# CarPower.net
KiCad netlist of a schematic drawn in Altium Designer
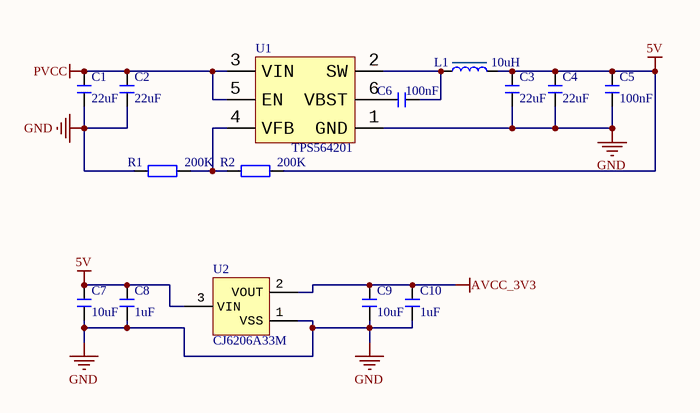
[diagram p0: CarPower.SchDoc]

(export (version "E")
  (design (tool "Eeschema 10.0.6"))
  (components
    (comp (ref "C1")
      (value "22uF")
      (footprint "C 0805_L")
      (description "无极性贴片电容")
      (fields (field (name "版权归属") "源创客"))
      (libsource (lib "3.1   - 电阻-电容-电感") (part "C"))
    )
    (comp (ref "C2")
      (value "22uF")
      (footprint "C 0805_L")
      (description "无极性贴片电容")
      (fields (field (name "版权归属") "源创客"))
      (libsource (lib "3.1   - 电阻-电容-电感") (part "C"))
    )
    (comp (ref "C3")
      (value "22uF")
      (footprint "C 0603_L")
      (description "无极性贴片电容")
      (fields (field (name "版权归属") "源创客"))
      (libsource (lib "3.1   - 电阻-电容-电感") (part "C"))
    )
    (comp (ref "C4")
      (value "22uF")
      (footprint "C 0603_L")
      (description "无极性贴片电容")
      (fields (field (name "版权归属") "源创客"))
      (libsource (lib "3.1   - 电阻-电容-电感") (part "C"))
    )
    (comp (ref "C5")
      (value "100nF")
      (footprint "C 0402_L")
      (description "无极性贴片电容")
      (fields (field (name "版权归属") "源创客"))
      (libsource (lib "3.1   - 电阻-电容-电感") (part "C"))
    )
    (comp (ref "C6")
      (value "100nF")
      (footprint "C 0402_L")
      (description "无极性贴片电容")
      (fields (field (name "版权归属") "源创客"))
      (libsource (lib "3.1   - 电阻-电容-电感") (part "C"))
    )
    (comp (ref "C7")
      (value "10uF")
      (footprint "C 0402_L")
      (description "无极性贴片电容")
      (fields (field (name "版权归属") "源创客"))
      (libsource (lib "3.1   - 电阻-电容-电感") (part "C"))
    )
    (comp (ref "C8")
      (value "1uF")
      (footprint "C 0402_L")
      (description "无极性贴片电容")
      (fields (field (name "版权归属") "源创客"))
      (libsource (lib "3.1   - 电阻-电容-电感") (part "C"))
    )
    (comp (ref "C9")
      (value "10uF")
      (footprint "C 0402_L")
      (description "无极性贴片电容")
      (fields (field (name "版权归属") "源创客"))
      (libsource (lib "3.1   - 电阻-电容-电感") (part "C"))
    )
    (comp (ref "C10")
      (value "1uF")
      (footprint "C 0402_L")
      (description "无极性贴片电容")
      (fields (field (name "版权归属") "源创客"))
      (libsource (lib "3.1   - 电阻-电容-电感") (part "C"))
    )
    (comp (ref "L1")
      (value "10uH")
      (footprint "L-0630")
      (description "贴片功率电感")
      (fields (field (name "版权归属") "源创客"))
      (libsource (lib "3.1   - 电阻-电容-电感") (part "L-CD"))
    )
    (comp (ref "R1")
      (value "200K")
      (footprint "R 0402_L")
      (description "贴片电阻")
      (fields (field (name "版权归属") "源创客"))
      (libsource (lib "3.1   - 电阻-电容-电感") (part "R"))
    )
    (comp (ref "R2")
      (value "200K")
      (footprint "R 0402_L")
      (description "贴片电阻")
      (fields (field (name "版权归属") "源创客"))
      (libsource (lib "3.1   - 电阻-电容-电感") (part "R"))
    )
    (comp (ref "U1")
      (value "TPS564201")
      (footprint "SOT23-6L")
      (description "3A  4.5V-17V输入 同步")
      (libsource (lib "1.3   - 电源类芯片") (part "TPS563200"))
    )
    (comp (ref "U2")
      (value "CJ6206A33M")
      (footprint "SOT23-3L")
      (description "三端稳压芯片\r\n6V 250mA")
      (libsource (lib "1.3   - 电源类芯片") (part "LN6206PXXX"))
    )
  )
  (nets
    (net (code "1") (name "5V") (class "Default")
      (node (ref "C3") (pin "2") (pinfunction "2_2") (pintype "passive"))
      (node (ref "C4") (pin "2") (pinfunction "2_2") (pintype "passive"))
      (node (ref "C5") (pin "2") (pinfunction "2_2") (pintype "passive"))
      (node (ref "C7") (pin "2") (pinfunction "2_2") (pintype "passive"))
      (node (ref "C8") (pin "2") (pinfunction "2_2") (pintype "passive"))
      (node (ref "L1") (pin "2") (pinfunction "2_2") (pintype "passive"))
      (node (ref "R2") (pin "2") (pinfunction "2_2") (pintype "passive"))
      (node (ref "U2") (pin "3") (pinfunction "VIN_3") (pintype "passive"))
    )
    (net (code "2") (name "AVCC_3V3") (class "Default")
      (node (ref "C10") (pin "2") (pinfunction "2_2") (pintype "passive"))
      (node (ref "C9") (pin "2") (pinfunction "2_2") (pintype "passive"))
      (node (ref "U2") (pin "2") (pinfunction "VOUT_2") (pintype "passive"))
    )
    (net (code "3") (name "GND") (class "Default")
      (node (ref "C1") (pin "1") (pinfunction "1_1") (pintype "passive"))
      (node (ref "C10") (pin "1") (pinfunction "1_1") (pintype "passive"))
      (node (ref "C2") (pin "1") (pinfunction "1_1") (pintype "passive"))
      (node (ref "C3") (pin "1") (pinfunction "1_1") (pintype "passive"))
      (node (ref "C4") (pin "1") (pinfunction "1_1") (pintype "passive"))
      (node (ref "C5") (pin "1") (pinfunction "1_1") (pintype "passive"))
      (node (ref "C7") (pin "1") (pinfunction "1_1") (pintype "passive"))
      (node (ref "C8") (pin "1") (pinfunction "1_1") (pintype "passive"))
      (node (ref "C9") (pin "1") (pinfunction "1_1") (pintype "passive"))
      (node (ref "R1") (pin "1") (pinfunction "1_1") (pintype "passive"))
      (node (ref "U1") (pin "1") (pinfunction "GND_1") (pintype "passive"))
      (node (ref "U2") (pin "1") (pinfunction "VSS_1") (pintype "passive"))
    )
    (net (code "4") (name "Net-(U1-SW)") (class "Default")
      (node (ref "C6") (pin "2") (pinfunction "2_2") (pintype "passive"))
      (node (ref "L1") (pin "1") (pinfunction "1_1") (pintype "passive"))
      (node (ref "U1") (pin "2") (pinfunction "SW_2") (pintype "passive"))
    )
    (net (code "5") (name "Net-(U1-VBST)") (class "Default")
      (node (ref "C6") (pin "1") (pinfunction "1_1") (pintype "passive"))
      (node (ref "U1") (pin "6") (pinfunction "VBST_6") (pintype "passive"))
    )
    (net (code "6") (name "Net-(U1-VFB)") (class "Default")
      (node (ref "R1") (pin "2") (pinfunction "2_2") (pintype "passive"))
      (node (ref "R2") (pin "1") (pinfunction "1_1") (pintype "passive"))
      (node (ref "U1") (pin "4") (pinfunction "VFB_4") (pintype "passive"))
    )
    (net (code "7") (name "PVCC") (class "Default")
      (node (ref "C1") (pin "2") (pinfunction "2_2") (pintype "passive"))
      (node (ref "C2") (pin "2") (pinfunction "2_2") (pintype "passive"))
      (node (ref "U1") (pin "3") (pinfunction "VIN_3") (pintype "passive"))
      (node (ref "U1") (pin "5") (pinfunction "EN_5") (pintype "passive"))
    )
  )
)
